# tunnelAmp_AD_ASCII.net
KiCad netlist of a schematic drawn in Altium Designer
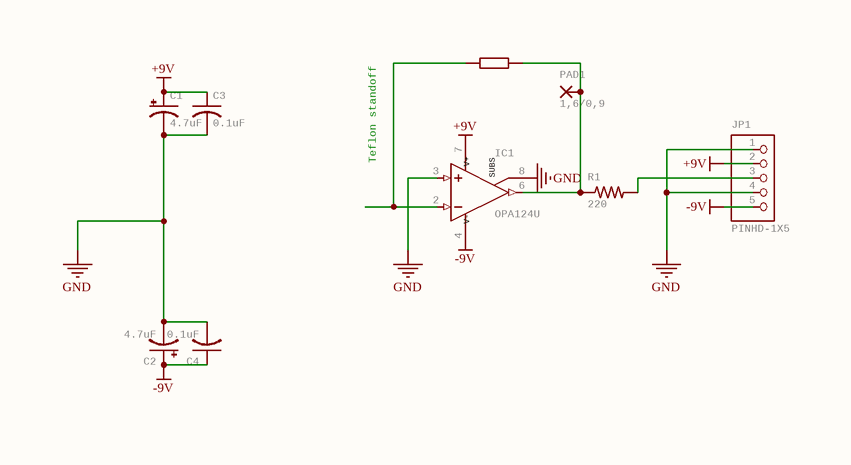
[diagram p0: tunnelAmp_AD_ASCII.SchDoc]

(export (version "E")
  (design (tool "Eeschema 10.0.6"))
  (components
    (comp (ref "C1")
      (value "4.7uF")
      (footprint "C/6032-28W")
      (description "POLARIZED CAPACITOR, American symbol")
      (libsource (lib "resistor") (part "CPOL-USC/6032-28W"))
    )
    (comp (ref "C2")
      (value "4.7uF")
      (footprint "C/6032-28W")
      (description "POLARIZED CAPACITOR, American symbol")
      (libsource (lib "") (part "CPOL-USC/6032-28W_1"))
    )
    (comp (ref "C3")
      (value "0.1uF")
      (footprint "C0603")
      (description "CAPACITOR, American symbol")
      (libsource (lib "resistor") (part "C-USC0603"))
    )
    (comp (ref "C4")
      (value "0.1uF")
      (footprint "C0603")
      (description "CAPACITOR, American symbol")
      (libsource (lib "resistor") (part "C-USC0603"))
    )
    (comp (ref "IC1")
      (value "OPA124U")
      (footprint "SO08")
      (description "Difet Operational Amplifier")
      (fields
        (field (name "V+") "V+")
        (field (name "V-") "V-")
        (field (name "SUBS") "SUBS")
        (field (name "LIBRARYNAME") "burr-brown")
      )
      (libsource (lib "burr-brown") (part "OPA124U"))
    )
    (comp (ref "JP1")
      (value "PINHD-1X5")
      (footprint "1X05")
      (description "PIN HEADER")
      (fields (field (name "LIBRARYNAME") "pinhead"))
      (libsource (lib "pinhead") (part "PINHD-1X5"))
    )
    (comp (ref "PAD1")
      (value "1,6/0,9")
      (footprint "1,6/0,9")
      (description "THROUGH-HOLE PAD")
      (fields (field (name "LIBRARYNAME") "wirepad"))
      (libsource (lib "wirepad") (part "1,6/0,9"))
    )
    (comp (ref "R1")
      (value "220")
      (footprint "R0603")
      (description "RESISTOR, American symbol")
      (libsource (lib "resistor") (part "R-US_R0603"))
    )
    (comp (ref "R3")
      (value "100M")
      (description "RESISTOR")
      (fields (field (name "LIBRARYNAME") "docu-dummy"))
      (libsource (lib "docu-dummy") (part "R"))
    )
  )
  (nets
    (net (code "1") (name "+9V") (class "Default")
      (node (ref "C1") (pin "+") (pinfunction "+_+") (pintype "passive"))
      (node (ref "C3") (pin "1") (pinfunction "1_1") (pintype "passive"))
      (node (ref "IC1") (pin "7") (pinfunction "V+_7") (pintype "power_in"))
      (node (ref "JP1") (pin "2") (pinfunction "2_2") (pintype "passive"))
    )
    (net (code "2") (name "-9V") (class "Default")
      (node (ref "C2") (pin "+") (pinfunction "+_+") (pintype "passive"))
      (node (ref "C4") (pin "1") (pinfunction "1_1") (pintype "passive"))
      (node (ref "IC1") (pin "4") (pinfunction "V-_4") (pintype "power_in"))
      (node (ref "JP1") (pin "5") (pinfunction "5_5") (pintype "passive"))
    )
    (net (code "3") (name "GND") (class "Default")
      (node (ref "C1") (pin "-") (pinfunction "-_-") (pintype "passive"))
      (node (ref "C2") (pin "-") (pinfunction "-_-") (pintype "passive"))
      (node (ref "C3") (pin "2") (pinfunction "2_2") (pintype "passive"))
      (node (ref "C4") (pin "2") (pinfunction "2_2") (pintype "passive"))
      (node (ref "IC1") (pin "3") (pinfunction "+IN_3") (pintype "input"))
      (node (ref "IC1") (pin "8") (pinfunction "SUBS_8") (pintype "passive"))
      (node (ref "JP1") (pin "1") (pinfunction "1_1") (pintype "passive"))
      (node (ref "JP1") (pin "4") (pinfunction "4_4") (pintype "passive"))
    )
    (net (code "4") (name "Net-(IC1-OUT)") (class "Default")
      (node (ref "IC1") (pin "6") (pinfunction "OUT_6") (pintype "output"))
      (node (ref "PAD1") (pin "1") (pinfunction "P_1") (pintype "passive"))
      (node (ref "R1") (pin "1") (pinfunction "1_1") (pintype "passive"))
    )
    (net (code "5") (name "Net-(JP1-Pad3)") (class "Default")
      (node (ref "JP1") (pin "3") (pinfunction "3_3") (pintype "passive"))
      (node (ref "R1") (pin "2") (pinfunction "2_2") (pintype "passive"))
    )
    (net (code "6") (name "unconnected-(IC1--IN-Pad2)") (class "Default")
      (node (ref "IC1") (pin "2") (pinfunction "-IN_2") (pintype "input"))
    )
  )
)
